# LVDS_TX.net
KiCad netlist of a schematic drawn in Altium Designer
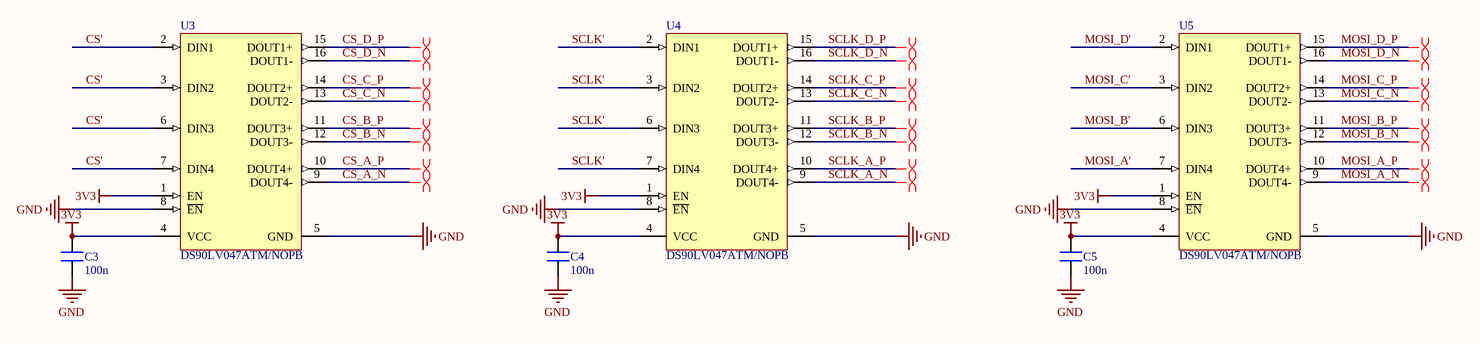
[diagram p0: LVDS_TX.SchDoc]

(export (version "E")
  (design (tool "Eeschema 10.0.6"))
  (components
    (comp (ref "C3") (value "100n") (footprint "C 0402_L") (libsource (lib "ZYNQ_开发板") (part "C_1")))
    (comp (ref "C4") (value "100n") (footprint "C 0402_L") (libsource (lib "ZYNQ_开发板") (part "C_1")))
    (comp (ref "C5") (value "100n") (footprint "C 0402_L") (libsource (lib "ZYNQ_开发板") (part "C_1")))
    (comp (ref "U3")
      (value "DS90LV047ATM/NOPB")
      (footprint "D0016A_L")
      (description "3V LVDS Quad CMOS Differential Line Driver, 16-pin Narrow SOIC, Pb-Free")
      (fields (field (name "MANUFACTURER") "Texas Instruments"))
      (libsource (lib "Altium Content Vault") (part "IN-LNDRV-DS90LV047ATM"))
    )
    (comp (ref "U4")
      (value "DS90LV047ATM/NOPB")
      (footprint "D0016A_L")
      (description "3V LVDS Quad CMOS Differential Line Driver, 16-pin Narrow SOIC, Pb-Free")
      (fields (field (name "MANUFACTURER") "Texas Instruments"))
      (libsource (lib "Altium Content Vault") (part "IN-LNDRV-DS90LV047ATM"))
    )
    (comp (ref "U5")
      (value "DS90LV047ATM/NOPB")
      (footprint "D0016A_L")
      (description "3V LVDS Quad CMOS Differential Line Driver, 16-pin Narrow SOIC, Pb-Free")
      (fields (field (name "MANUFACTURER") "Texas Instruments"))
      (libsource (lib "Altium Content Vault") (part "IN-LNDRV-DS90LV047ATM"))
    )
  )
  (nets
    (net (code "1") (name "/CS'") (class "Default")
      (node (ref "U3") (pin "2") (pinfunction "DIN1_2") (pintype "input"))
      (node (ref "U3") (pin "3") (pinfunction "DIN2_3") (pintype "input"))
      (node (ref "U3") (pin "6") (pinfunction "DIN3_6") (pintype "input"))
      (node (ref "U3") (pin "7") (pinfunction "DIN4_7") (pintype "input"))
    )
    (net (code "2") (name "/CS_A_N") (class "Default")
      (node (ref "U3") (pin "9") (pinfunction "DOUT4-_9") (pintype "output"))
    )
    (net (code "3") (name "/CS_A_P") (class "Default")
      (node (ref "U3") (pin "10") (pinfunction "DOUT4+_10") (pintype "output"))
    )
    (net (code "4") (name "/CS_B_N") (class "Default")
      (node (ref "U3") (pin "12") (pinfunction "DOUT3-_12") (pintype "output"))
    )
    (net (code "5") (name "/CS_B_P") (class "Default")
      (node (ref "U3") (pin "11") (pinfunction "DOUT3+_11") (pintype "output"))
    )
    (net (code "6") (name "/CS_C_N") (class "Default")
      (node (ref "U3") (pin "13") (pinfunction "DOUT2-_13") (pintype "output"))
    )
    (net (code "7") (name "/CS_C_P") (class "Default")
      (node (ref "U3") (pin "14") (pinfunction "DOUT2+_14") (pintype "output"))
    )
    (net (code "8") (name "/CS_D_N") (class "Default")
      (node (ref "U3") (pin "16") (pinfunction "DOUT1-_16") (pintype "output"))
    )
    (net (code "9") (name "/CS_D_P") (class "Default")
      (node (ref "U3") (pin "15") (pinfunction "DOUT1+_15") (pintype "output"))
    )
    (net (code "10") (name "/MOSI_A'") (class "Default")
      (node (ref "U5") (pin "7") (pinfunction "DIN4_7") (pintype "input"))
    )
    (net (code "11") (name "/MOSI_A_N") (class "Default")
      (node (ref "U5") (pin "9") (pinfunction "DOUT4-_9") (pintype "output"))
    )
    (net (code "12") (name "/MOSI_A_P") (class "Default")
      (node (ref "U5") (pin "10") (pinfunction "DOUT4+_10") (pintype "output"))
    )
    (net (code "13") (name "/MOSI_B'") (class "Default")
      (node (ref "U5") (pin "6") (pinfunction "DIN3_6") (pintype "input"))
    )
    (net (code "14") (name "/MOSI_B_N") (class "Default")
      (node (ref "U5") (pin "12") (pinfunction "DOUT3-_12") (pintype "output"))
    )
    (net (code "15") (name "/MOSI_B_P") (class "Default")
      (node (ref "U5") (pin "11") (pinfunction "DOUT3+_11") (pintype "output"))
    )
    (net (code "16") (name "/MOSI_C'") (class "Default")
      (node (ref "U5") (pin "3") (pinfunction "DIN2_3") (pintype "input"))
    )
    (net (code "17") (name "/MOSI_C_N") (class "Default")
      (node (ref "U5") (pin "13") (pinfunction "DOUT2-_13") (pintype "output"))
    )
    (net (code "18") (name "/MOSI_C_P") (class "Default")
      (node (ref "U5") (pin "14") (pinfunction "DOUT2+_14") (pintype "output"))
    )
    (net (code "19") (name "/MOSI_D'") (class "Default")
      (node (ref "U5") (pin "2") (pinfunction "DIN1_2") (pintype "input"))
    )
    (net (code "20") (name "/MOSI_D_N") (class "Default")
      (node (ref "U5") (pin "16") (pinfunction "DOUT1-_16") (pintype "output"))
    )
    (net (code "21") (name "/MOSI_D_P") (class "Default")
      (node (ref "U5") (pin "15") (pinfunction "DOUT1+_15") (pintype "output"))
    )
    (net (code "22") (name "/SCLK'") (class "Default")
      (node (ref "U4") (pin "2") (pinfunction "DIN1_2") (pintype "input"))
      (node (ref "U4") (pin "3") (pinfunction "DIN2_3") (pintype "input"))
      (node (ref "U4") (pin "6") (pinfunction "DIN3_6") (pintype "input"))
      (node (ref "U4") (pin "7") (pinfunction "DIN4_7") (pintype "input"))
    )
    (net (code "23") (name "/SCLK_A_N") (class "Default")
      (node (ref "U4") (pin "9") (pinfunction "DOUT4-_9") (pintype "output"))
    )
    (net (code "24") (name "/SCLK_A_P") (class "Default")
      (node (ref "U4") (pin "10") (pinfunction "DOUT4+_10") (pintype "output"))
    )
    (net (code "25") (name "/SCLK_B_N") (class "Default")
      (node (ref "U4") (pin "12") (pinfunction "DOUT3-_12") (pintype "output"))
    )
    (net (code "26") (name "/SCLK_B_P") (class "Default")
      (node (ref "U4") (pin "11") (pinfunction "DOUT3+_11") (pintype "output"))
    )
    (net (code "27") (name "/SCLK_C_N") (class "Default")
      (node (ref "U4") (pin "13") (pinfunction "DOUT2-_13") (pintype "output"))
    )
    (net (code "28") (name "/SCLK_C_P") (class "Default")
      (node (ref "U4") (pin "14") (pinfunction "DOUT2+_14") (pintype "output"))
    )
    (net (code "29") (name "/SCLK_D_N") (class "Default")
      (node (ref "U4") (pin "16") (pinfunction "DOUT1-_16") (pintype "output"))
    )
    (net (code "30") (name "/SCLK_D_P") (class "Default")
      (node (ref "U4") (pin "15") (pinfunction "DOUT1+_15") (pintype "output"))
    )
    (net (code "31") (name "3V3") (class "Default")
      (node (ref "C3") (pin "2") (pintype "passive"))
      (node (ref "C4") (pin "2") (pintype "passive"))
      (node (ref "C5") (pin "2") (pintype "passive"))
      (node (ref "U3") (pin "1") (pinfunction "EN_1") (pintype "input"))
      (node (ref "U3") (pin "4") (pinfunction "VCC_4") (pintype "power_in"))
      (node (ref "U4") (pin "1") (pinfunction "EN_1") (pintype "input"))
      (node (ref "U4") (pin "4") (pinfunction "VCC_4") (pintype "power_in"))
      (node (ref "U5") (pin "1") (pinfunction "EN_1") (pintype "input"))
      (node (ref "U5") (pin "4") (pinfunction "VCC_4") (pintype "power_in"))
    )
    (net (code "32") (name "GND") (class "Default")
      (node (ref "C3") (pin "1") (pintype "passive"))
      (node (ref "C4") (pin "1") (pintype "passive"))
      (node (ref "C5") (pin "1") (pintype "passive"))
      (node (ref "U3") (pin "5") (pinfunction "GND_5") (pintype "power_in"))
      (node (ref "U3") (pin "8") (pinfunction "~{EN}_8") (pintype "input"))
      (node (ref "U4") (pin "5") (pinfunction "GND_5") (pintype "power_in"))
      (node (ref "U4") (pin "8") (pinfunction "~{EN}_8") (pintype "input"))
      (node (ref "U5") (pin "5") (pinfunction "GND_5") (pintype "power_in"))
      (node (ref "U5") (pin "8") (pinfunction "~{EN}_8") (pintype "input"))
    )
  )
)
